# SCH.net
KiCad netlist of a schematic drawn in EasyEDA
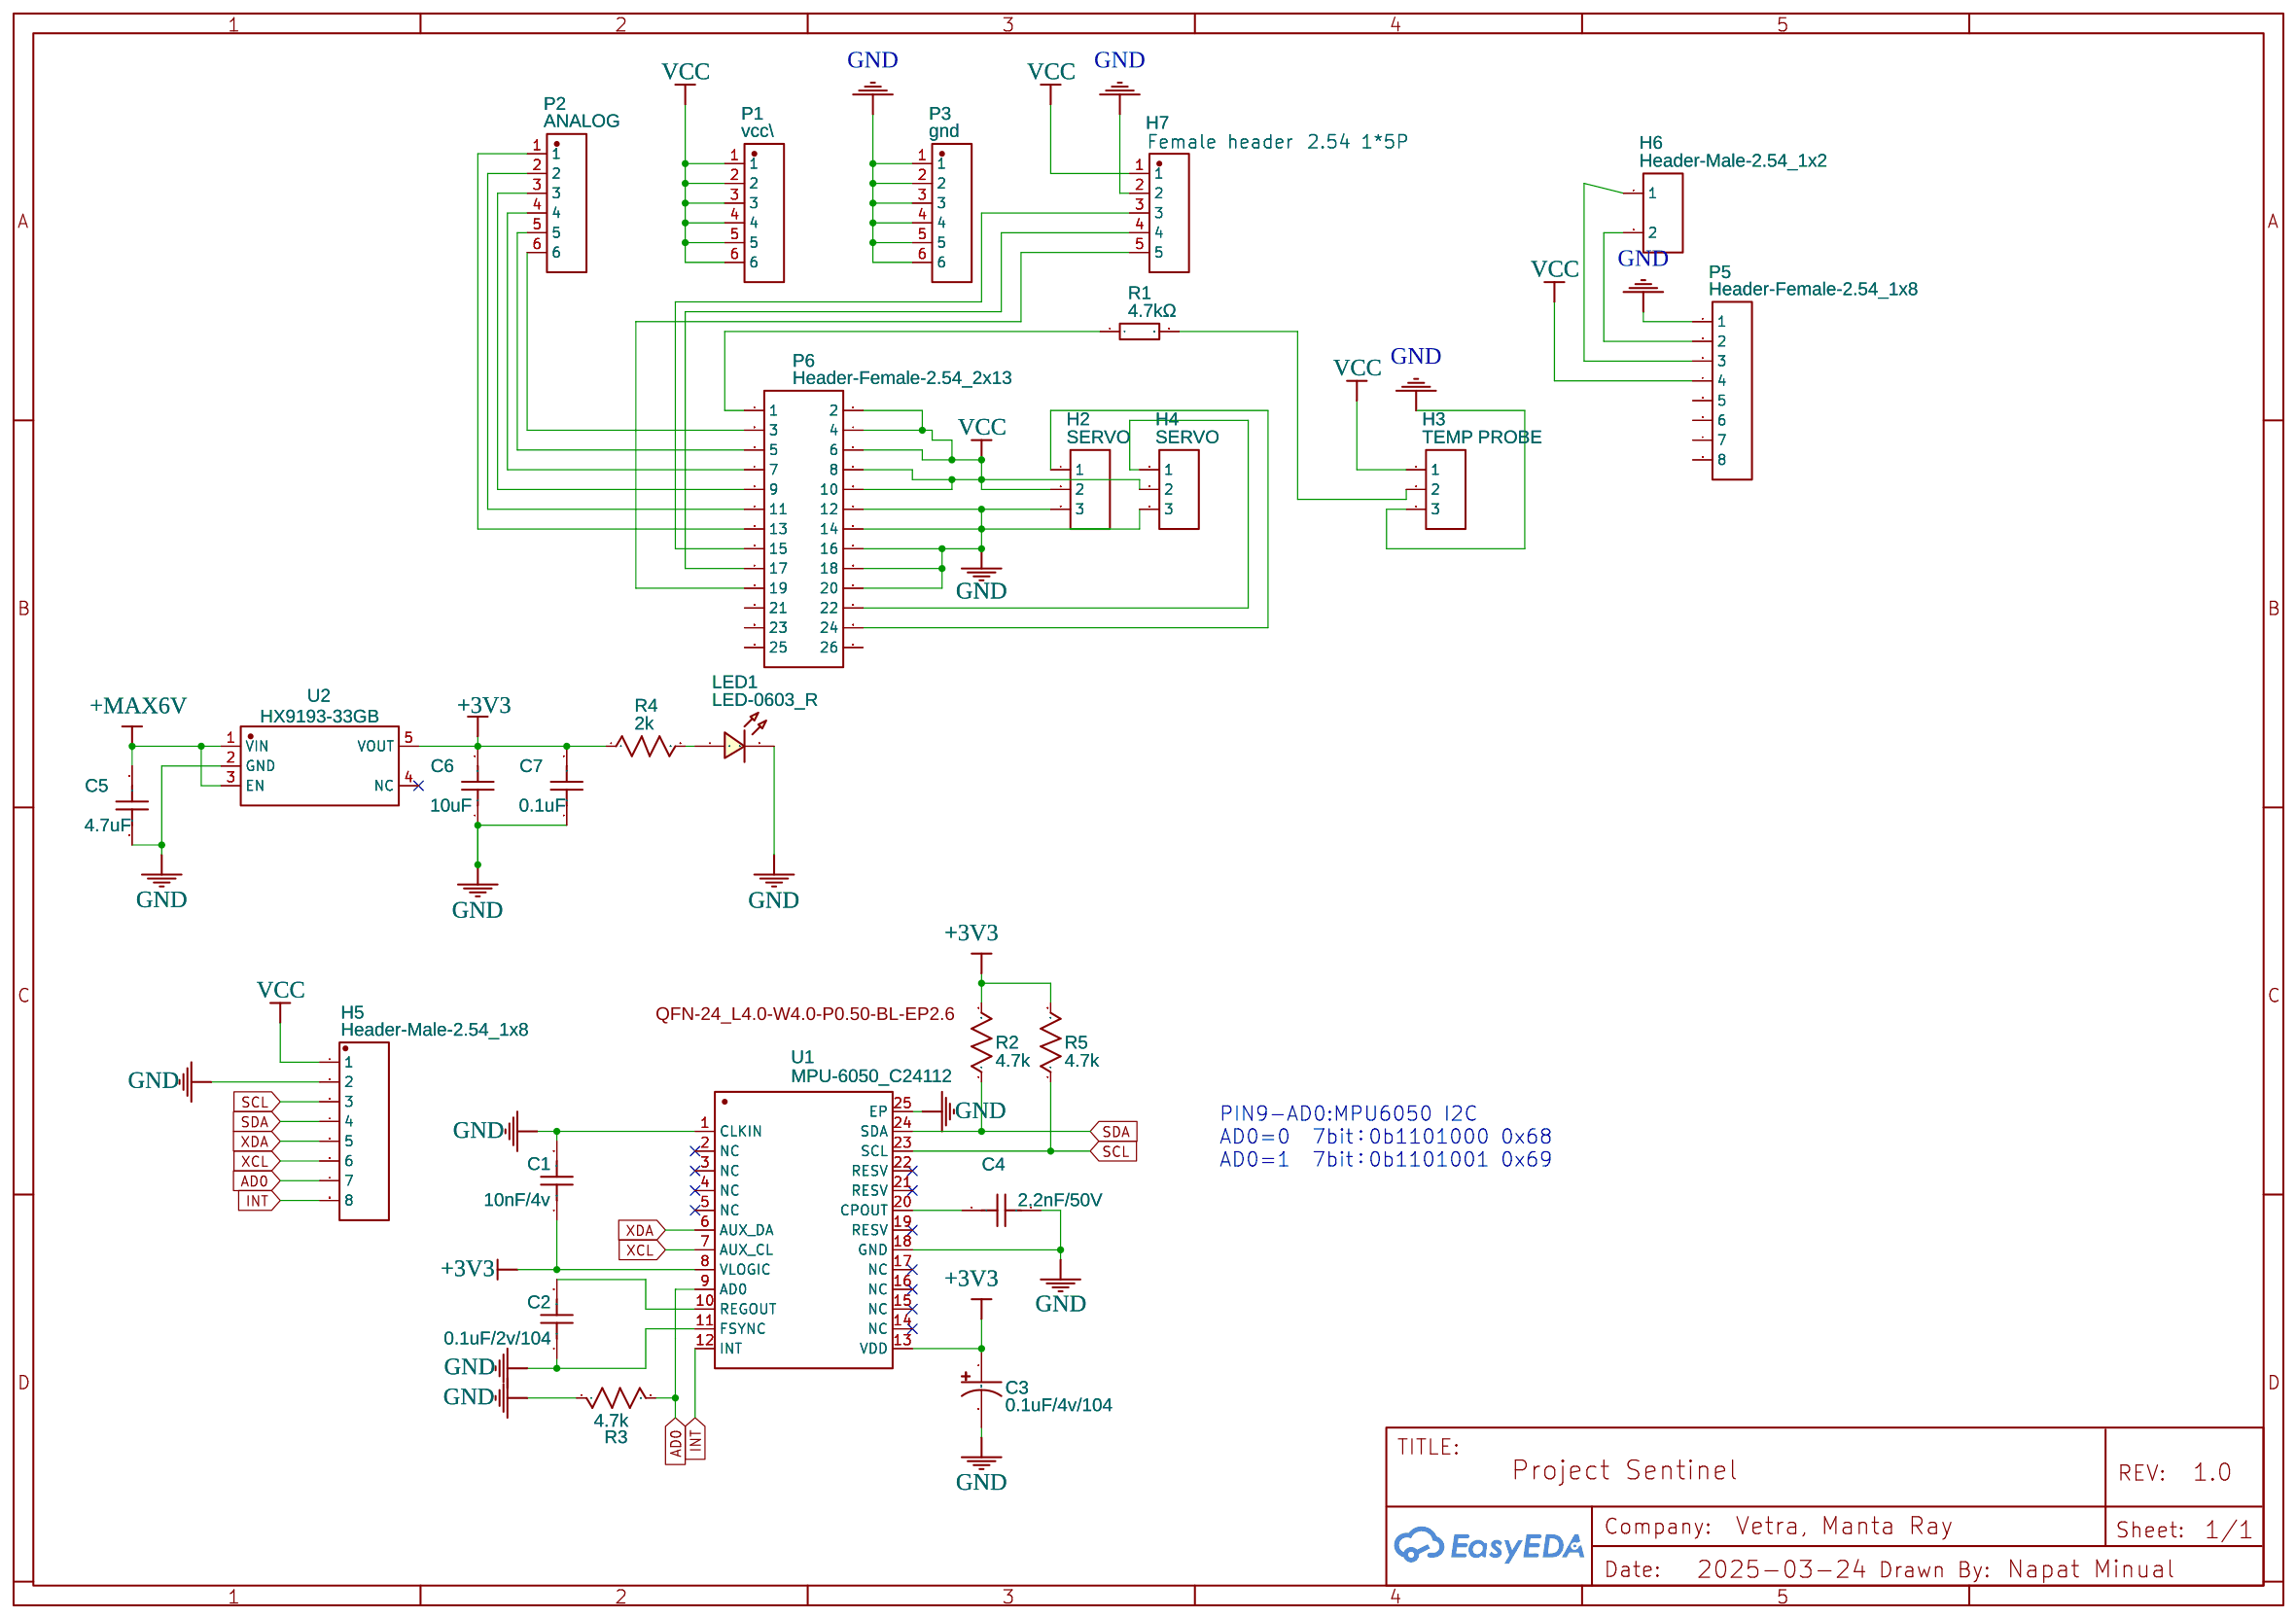
[diagram p0: schematic sheet]

(export (version "E")
  (design (tool "Eeschema 10.0.6"))
  (components
    (comp (ref "C1") (value "10nF/4v") (libsource (lib "") (part "C_0603_US_1")))
    (comp (ref "C2") (value "0.1uF/2v/104") (libsource (lib "") (part "C_0603_US_1")))
    (comp (ref "C3")
      (value "0.1uF/4v/104")
      (fields (field (name "Manufacturer Part") "TPSA106K016R1000") (field (name "Manufacturer") "AVX"))
      (libsource (lib "") (part "TPSA106K016R1000_C282116"))
    )
    (comp (ref "C4") (value "2.2nF/50V") (libsource (lib "") (part "C_0603_US")))
    (comp (ref "C5") (value "4.7uF") (libsource (lib "") (part "C_0603_US_1")))
    (comp (ref "C6") (value "10uF") (libsource (lib "") (part "C_0603_US_1")))
    (comp (ref "C7") (value "0.1uF") (libsource (lib "") (part "C_0603_US_1")))
    (comp (ref "H2")
      (value "SERVO")
      (fields (field (name "Manufacturer Part") "2.54-1*3P针") (field (name "Manufacturer") "BOOMELE(博穆精密)"))
      (libsource (lib "") (part "Header-Male-2.54_1x3"))
    )
    (comp (ref "H3")
      (value "TEMP PROBE")
      (fields (field (name "Manufacturer Part") "2.54-1*3P针") (field (name "Manufacturer") "BOOMELE(博穆精密)"))
      (libsource (lib "") (part "Header-Male-2.54_1x3"))
    )
    (comp (ref "H4")
      (value "SERVO")
      (fields (field (name "Manufacturer Part") "2.54-1*3P针") (field (name "Manufacturer") "BOOMELE(博穆精密)"))
      (libsource (lib "") (part "Header-Male-2.54_1x3"))
    )
    (comp (ref "H5")
      (value "Header-Male-2.54_1x8")
      (fields (field (name "Manufacturer Part") "B-2100S08P-A110") (field (name "Manufacturer") "Ckmtw(灿科盟)"))
      (libsource (lib "") (part "Header-Male-2.54_1x8"))
    )
    (comp (ref "H6")
      (value "Header-Male-2.54_1x2")
      (fields
        (field (name "Manufacturer Part") "826629-2")
        (field (name "Manufacturer") "TE Connectivity(泰科电子)")
      )
      (libsource (lib "") (part "Header-Male-2.54_1x2"))
    )
    (comp (ref "H7")
      (value "Female header　2.54 1*5Ｐ")
      (fields (field (name "Manufacturer Part") "排母　2.54 1*5Ｐ"))
      (libsource (lib "") (part "Female header　2.54 1*5Ｐ"))
    )
    (comp (ref "LED1")
      (value "LED-0603_R")
      (fields
        (field (name "Manufacturer Part") "19-217/R6C-AL1M2VY/3T")
        (field (name "Manufacturer") "EVERLIGHT(台湾亿光)")
      )
      (libsource (lib "") (part "LED-0603_R"))
    )
    (comp (ref "P1")
      (value "vcc\\")
      (fields (field (name "Manufacturer Part") "2.54-1*6P母") (field (name "Manufacturer") "BOOMELE(博穆精密)"))
      (libsource (lib "") (part "Header-Female-2.54_1x6"))
    )
    (comp (ref "P2")
      (value "ANALOG")
      (fields (field (name "Manufacturer Part") "2.54-1*6P母") (field (name "Manufacturer") "BOOMELE(博穆精密)"))
      (libsource (lib "") (part "Header-Female-2.54_1x6"))
    )
    (comp (ref "P3")
      (value "gnd")
      (fields (field (name "Manufacturer Part") "2.54-1*6P母") (field (name "Manufacturer") "BOOMELE(博穆精密)"))
      (libsource (lib "") (part "Header-Female-2.54_1x6"))
    )
    (comp (ref "P5")
      (value "Header-Female-2.54_1x8")
      (fields (field (name "Manufacturer Part") "2.54-1*8P母环保") (field (name "Manufacturer") "BOOMELE(博穆精密)"))
      (libsource (lib "") (part "Header-Female-2.54_1x8"))
    )
    (comp (ref "P6")
      (value "Header-Female-2.54_2x13")
      (fields (field (name "Manufacturer Part") "2.54-2*13P母") (field (name "Manufacturer") "BOOMELE(博穆精密)"))
      (libsource (lib "") (part "Header-Female-2.54_2x13"))
    )
    (comp (ref "R1")
      (value "4.7kΩ")
      (fields (field (name "Manufacturer Part") "RMC20104.7K1%N") (field (name "Manufacturer") "Tyohm(幸亚电阻)"))
      (libsource (lib "") (part "RMC20104.7K1%N"))
    )
    (comp (ref "R2") (value "4.7k") (libsource (lib "") (part "R_0603_US")))
    (comp (ref "R3") (value "4.7k") (libsource (lib "") (part "R_0603_US_1")))
    (comp (ref "R4") (value "2k") (libsource (lib "") (part "R_0603_US_2")))
    (comp (ref "R5") (value "4.7k") (libsource (lib "") (part "R_0603_US")))
    (comp (ref "U1")
      (value "MPU-6050_C24112")
      (fields (field (name "Manufacturer Part") "MPU-6050") (field (name "Manufacturer") "InvenSense"))
      (libsource (lib "") (part "MPU-6050_C24112"))
    )
    (comp (ref "U2")
      (value "HX9193-33GB")
      (fields (field (name "Manufacturer") "hengjiaxing"))
      (libsource (lib "") (part "HX9193-33GB"))
    )
  )
  (nets
    (net (code "1") (name "+3V3") (class "Default")
      (node (ref "C1") (pin "1") (pinfunction "1_1") (pintype "unspecified"))
      (node (ref "C3") (pin "1") (pinfunction "1_1") (pintype "unspecified"))
      (node (ref "C6") (pin "2") (pinfunction "2_2") (pintype "unspecified"))
      (node (ref "C7") (pin "2") (pinfunction "2_2") (pintype "unspecified"))
      (node (ref "R2") (pin "2") (pinfunction "2_2") (pintype "unspecified"))
      (node (ref "R4") (pin "1") (pinfunction "1_1") (pintype "unspecified"))
      (node (ref "R5") (pin "2") (pinfunction "2_2") (pintype "unspecified"))
      (node (ref "U1") (pin "13") (pinfunction "VDD_13") (pintype "unspecified"))
      (node (ref "U1") (pin "8") (pinfunction "VLOGIC_8") (pintype "unspecified"))
      (node (ref "U2") (pin "5") (pinfunction "VOUT_5") (pintype "unspecified"))
    )
    (net (code "2") (name "+MAX6V") (class "Default")
      (node (ref "C5") (pin "2") (pinfunction "2_2") (pintype "unspecified"))
      (node (ref "U2") (pin "1") (pinfunction "VIN_1") (pintype "unspecified"))
      (node (ref "U2") (pin "3") (pinfunction "EN_3") (pintype "unspecified"))
    )
    (net (code "3") (name "AD0") (class "Default")
      (node (ref "H5") (pin "7") (pinfunction "7_7") (pintype "unspecified"))
      (node (ref "R3") (pin "2") (pinfunction "2_2") (pintype "unspecified"))
      (node (ref "U1") (pin "9") (pinfunction "AD0_9") (pintype "unspecified"))
    )
    (net (code "4") (name "GND") (class "Default")
      (node (ref "C1") (pin "2") (pinfunction "2_2") (pintype "unspecified"))
      (node (ref "C2") (pin "1") (pinfunction "1_1") (pintype "unspecified"))
      (node (ref "C3") (pin "2") (pinfunction "2_2") (pintype "unspecified"))
      (node (ref "C4") (pin "1") (pinfunction "1_1") (pintype "unspecified"))
      (node (ref "C5") (pin "1") (pinfunction "1_1") (pintype "unspecified"))
      (node (ref "C6") (pin "1") (pinfunction "1_1") (pintype "unspecified"))
      (node (ref "C7") (pin "1") (pinfunction "1_1") (pintype "unspecified"))
      (node (ref "H2") (pin "3") (pinfunction "3_3") (pintype "input"))
      (node (ref "H3") (pin "3") (pinfunction "3_3") (pintype "input"))
      (node (ref "H4") (pin "3") (pinfunction "3_3") (pintype "input"))
      (node (ref "H5") (pin "2") (pinfunction "2_2") (pintype "unspecified"))
      (node (ref "H7") (pin "2") (pinfunction "2_2") (pintype "unspecified"))
      (node (ref "LED1") (pin "2") (pinfunction "2_2") (pintype "unspecified"))
      (node (ref "P3") (pin "1") (pinfunction "1_1") (pintype "unspecified"))
      (node (ref "P3") (pin "2") (pinfunction "2_2") (pintype "unspecified"))
      (node (ref "P3") (pin "3") (pinfunction "3_3") (pintype "unspecified"))
      (node (ref "P3") (pin "4") (pinfunction "4_4") (pintype "unspecified"))
      (node (ref "P3") (pin "5") (pinfunction "5_5") (pintype "unspecified"))
      (node (ref "P3") (pin "6") (pinfunction "6_6") (pintype "unspecified"))
      (node (ref "P5") (pin "1") (pinfunction "1_1") (pintype "input"))
      (node (ref "P6") (pin "12") (pinfunction "12_12") (pintype "input"))
      (node (ref "P6") (pin "14") (pinfunction "14_14") (pintype "input"))
      (node (ref "P6") (pin "16") (pinfunction "16_16") (pintype "input"))
      (node (ref "P6") (pin "18") (pinfunction "18_18") (pintype "input"))
      (node (ref "P6") (pin "20") (pinfunction "20_20") (pintype "input"))
      (node (ref "R3") (pin "1") (pinfunction "1_1") (pintype "unspecified"))
      (node (ref "U1") (pin "1") (pinfunction "CLKIN_1") (pintype "unspecified"))
      (node (ref "U1") (pin "11") (pinfunction "FSYNC_11") (pintype "unspecified"))
      (node (ref "U1") (pin "18") (pinfunction "GND_18") (pintype "unspecified"))
      (node (ref "U1") (pin "25") (pinfunction "EP_25") (pintype "unspecified"))
      (node (ref "U2") (pin "2") (pinfunction "GND_2") (pintype "unspecified"))
    )
    (net (code "5") (name "INT") (class "Default")
      (node (ref "H5") (pin "8") (pinfunction "8_8") (pintype "unspecified"))
      (node (ref "U1") (pin "12") (pinfunction "INT_12") (pintype "unspecified"))
    )
    (net (code "6") (name "Net-(H2-Pad1)") (class "Default")
      (node (ref "H2") (pin "1") (pinfunction "1_1") (pintype "input"))
      (node (ref "P6") (pin "24") (pinfunction "24_24") (pintype "input"))
    )
    (net (code "7") (name "Net-(H3-Pad2)") (class "Default")
      (node (ref "H3") (pin "2") (pinfunction "2_2") (pintype "input"))
      (node (ref "R1") (pin "2") (pinfunction "2_2") (pintype "unspecified"))
    )
    (net (code "8") (name "Net-(H4-Pad1)") (class "Default")
      (node (ref "H4") (pin "1") (pinfunction "1_1") (pintype "input"))
      (node (ref "P6") (pin "22") (pinfunction "22_22") (pintype "input"))
    )
    (net (code "9") (name "Net-(H6-Pad1)") (class "Default")
      (node (ref "H6") (pin "1") (pinfunction "1_1") (pintype "unspecified"))
      (node (ref "P5") (pin "3") (pinfunction "3_3") (pintype "input"))
    )
    (net (code "10") (name "Net-(H6-Pad2)") (class "Default")
      (node (ref "H6") (pin "2") (pinfunction "2_2") (pintype "unspecified"))
      (node (ref "P5") (pin "2") (pinfunction "2_2") (pintype "input"))
    )
    (net (code "11") (name "Net-(H7-Pad3)") (class "Default")
      (node (ref "H7") (pin "3") (pinfunction "3_3") (pintype "unspecified"))
      (node (ref "P6") (pin "15") (pinfunction "15_15") (pintype "input"))
    )
    (net (code "12") (name "Net-(H7-Pad4)") (class "Default")
      (node (ref "H7") (pin "4") (pinfunction "4_4") (pintype "unspecified"))
      (node (ref "P6") (pin "17") (pinfunction "17_17") (pintype "input"))
    )
    (net (code "13") (name "Net-(H7-Pad5)") (class "Default")
      (node (ref "H7") (pin "5") (pinfunction "5_5") (pintype "unspecified"))
      (node (ref "P6") (pin "19") (pinfunction "19_19") (pintype "input"))
    )
    (net (code "14") (name "Net-(LED1-Pad1)") (class "Default")
      (node (ref "LED1") (pin "1") (pinfunction "1_1") (pintype "unspecified"))
      (node (ref "R4") (pin "2") (pinfunction "2_2") (pintype "unspecified"))
    )
    (net (code "15") (name "Net-(P2-Pad1)") (class "Default")
      (node (ref "P2") (pin "1") (pinfunction "1_1") (pintype "unspecified"))
      (node (ref "P6") (pin "13") (pinfunction "13_13") (pintype "input"))
    )
    (net (code "16") (name "Net-(P2-Pad2)") (class "Default")
      (node (ref "P2") (pin "2") (pinfunction "2_2") (pintype "unspecified"))
      (node (ref "P6") (pin "11") (pinfunction "11_11") (pintype "input"))
    )
    (net (code "17") (name "Net-(P2-Pad3)") (class "Default")
      (node (ref "P2") (pin "3") (pinfunction "3_3") (pintype "unspecified"))
      (node (ref "P6") (pin "9") (pinfunction "9_9") (pintype "input"))
    )
    (net (code "18") (name "Net-(P2-Pad4)") (class "Default")
      (node (ref "P2") (pin "4") (pinfunction "4_4") (pintype "unspecified"))
      (node (ref "P6") (pin "7") (pinfunction "7_7") (pintype "input"))
    )
    (net (code "19") (name "Net-(P2-Pad5)") (class "Default")
      (node (ref "P2") (pin "5") (pinfunction "5_5") (pintype "unspecified"))
      (node (ref "P6") (pin "5") (pinfunction "5_5") (pintype "input"))
    )
    (net (code "20") (name "Net-(P2-Pad6)") (class "Default")
      (node (ref "P2") (pin "6") (pinfunction "6_6") (pintype "unspecified"))
      (node (ref "P6") (pin "3") (pinfunction "3_3") (pintype "input"))
    )
    (net (code "21") (name "Net-(P6-Pad1)") (class "Default")
      (node (ref "P6") (pin "1") (pinfunction "1_1") (pintype "input"))
      (node (ref "R1") (pin "1") (pinfunction "1_1") (pintype "unspecified"))
    )
    (net (code "22") (name "Net-(U1-CPOUT)") (class "Default")
      (node (ref "C4") (pin "2") (pinfunction "2_2") (pintype "unspecified"))
      (node (ref "U1") (pin "20") (pinfunction "CPOUT_20") (pintype "unspecified"))
    )
    (net (code "23") (name "Net-(U1-REGOUT)") (class "Default")
      (node (ref "C2") (pin "2") (pinfunction "2_2") (pintype "unspecified"))
      (node (ref "U1") (pin "10") (pinfunction "REGOUT_10") (pintype "unspecified"))
    )
    (net (code "24") (name "SCL") (class "Default")
      (node (ref "H5") (pin "3") (pinfunction "3_3") (pintype "unspecified"))
      (node (ref "R5") (pin "1") (pinfunction "1_1") (pintype "unspecified"))
      (node (ref "U1") (pin "23") (pinfunction "SCL_23") (pintype "unspecified"))
    )
    (net (code "25") (name "SDA") (class "Default")
      (node (ref "H5") (pin "4") (pinfunction "4_4") (pintype "unspecified"))
      (node (ref "R2") (pin "1") (pinfunction "1_1") (pintype "unspecified"))
      (node (ref "U1") (pin "24") (pinfunction "SDA_24") (pintype "unspecified"))
    )
    (net (code "26") (name "VCC") (class "Default")
      (node (ref "H2") (pin "2") (pinfunction "2_2") (pintype "input"))
      (node (ref "H3") (pin "1") (pinfunction "1_1") (pintype "input"))
      (node (ref "H4") (pin "2") (pinfunction "2_2") (pintype "input"))
      (node (ref "H5") (pin "1") (pinfunction "1_1") (pintype "unspecified"))
      (node (ref "H7") (pin "1") (pinfunction "1_1") (pintype "unspecified"))
      (node (ref "P1") (pin "1") (pinfunction "1_1") (pintype "unspecified"))
      (node (ref "P1") (pin "2") (pinfunction "2_2") (pintype "unspecified"))
      (node (ref "P1") (pin "3") (pinfunction "3_3") (pintype "unspecified"))
      (node (ref "P1") (pin "4") (pinfunction "4_4") (pintype "unspecified"))
      (node (ref "P1") (pin "5") (pinfunction "5_5") (pintype "unspecified"))
      (node (ref "P1") (pin "6") (pinfunction "6_6") (pintype "unspecified"))
      (node (ref "P5") (pin "4") (pinfunction "4_4") (pintype "input"))
      (node (ref "P6") (pin "10") (pinfunction "10_10") (pintype "input"))
      (node (ref "P6") (pin "2") (pinfunction "2_2") (pintype "input"))
      (node (ref "P6") (pin "4") (pinfunction "4_4") (pintype "input"))
      (node (ref "P6") (pin "6") (pinfunction "6_6") (pintype "input"))
      (node (ref "P6") (pin "8") (pinfunction "8_8") (pintype "input"))
    )
    (net (code "27") (name "XCL") (class "Default")
      (node (ref "H5") (pin "6") (pinfunction "6_6") (pintype "unspecified"))
      (node (ref "U1") (pin "7") (pinfunction "AUX_CL_7") (pintype "unspecified"))
    )
    (net (code "28") (name "XDA") (class "Default")
      (node (ref "H5") (pin "5") (pinfunction "5_5") (pintype "unspecified"))
      (node (ref "U1") (pin "6") (pinfunction "AUX_DA_6") (pintype "unspecified"))
    )
    (net (code "29") (name "unconnected-(P5-Pad5)") (class "Default")
      (node (ref "P5") (pin "5") (pinfunction "5_5") (pintype "input"))
    )
    (net (code "30") (name "unconnected-(P5-Pad6)") (class "Default")
      (node (ref "P5") (pin "6") (pinfunction "6_6") (pintype "input"))
    )
    (net (code "31") (name "unconnected-(P5-Pad7)") (class "Default")
      (node (ref "P5") (pin "7") (pinfunction "7_7") (pintype "input"))
    )
    (net (code "32") (name "unconnected-(P5-Pad8)") (class "Default")
      (node (ref "P5") (pin "8") (pinfunction "8_8") (pintype "input"))
    )
    (net (code "33") (name "unconnected-(P6-Pad21)") (class "Default")
      (node (ref "P6") (pin "21") (pinfunction "21_21") (pintype "input"))
    )
    (net (code "34") (name "unconnected-(P6-Pad23)") (class "Default")
      (node (ref "P6") (pin "23") (pinfunction "23_23") (pintype "input"))
    )
    (net (code "35") (name "unconnected-(P6-Pad25)") (class "Default")
      (node (ref "P6") (pin "25") (pinfunction "25_25") (pintype "input"))
    )
    (net (code "36") (name "unconnected-(P6-Pad26)") (class "Default")
      (node (ref "P6") (pin "26") (pinfunction "26_26") (pintype "input"))
    )
    (net (code "37") (name "unconnected-(U1-NC-Pad2)") (class "Default")
      (node (ref "U1") (pin "2") (pinfunction "NC_2") (pintype "unspecified+no_connect"))
    )
    (net (code "38") (name "unconnected-(U1-NC-Pad3)") (class "Default")
      (node (ref "U1") (pin "3") (pinfunction "NC_3") (pintype "unspecified+no_connect"))
    )
    (net (code "39") (name "unconnected-(U1-NC-Pad4)") (class "Default")
      (node (ref "U1") (pin "4") (pinfunction "NC_4") (pintype "unspecified+no_connect"))
    )
    (net (code "40") (name "unconnected-(U1-NC-Pad5)") (class "Default")
      (node (ref "U1") (pin "5") (pinfunction "NC_5") (pintype "unspecified+no_connect"))
    )
    (net (code "41") (name "unconnected-(U1-NC-Pad14)") (class "Default")
      (node (ref "U1") (pin "14") (pinfunction "NC_14") (pintype "unspecified+no_connect"))
    )
    (net (code "42") (name "unconnected-(U1-NC-Pad15)") (class "Default")
      (node (ref "U1") (pin "15") (pinfunction "NC_15") (pintype "unspecified+no_connect"))
    )
    (net (code "43") (name "unconnected-(U1-NC-Pad16)") (class "Default")
      (node (ref "U1") (pin "16") (pinfunction "NC_16") (pintype "unspecified+no_connect"))
    )
    (net (code "44") (name "unconnected-(U1-NC-Pad17)") (class "Default")
      (node (ref "U1") (pin "17") (pinfunction "NC_17") (pintype "unspecified+no_connect"))
    )
    (net (code "45") (name "unconnected-(U1-RESV-Pad19)") (class "Default")
      (node (ref "U1") (pin "19") (pinfunction "RESV_19") (pintype "unspecified+no_connect"))
    )
    (net (code "46") (name "unconnected-(U1-RESV-Pad21)") (class "Default")
      (node (ref "U1") (pin "21") (pinfunction "RESV_21") (pintype "unspecified+no_connect"))
    )
    (net (code "47") (name "unconnected-(U1-RESV-Pad22)") (class "Default")
      (node (ref "U1") (pin "22") (pinfunction "RESV_22") (pintype "unspecified+no_connect"))
    )
    (net (code "48") (name "unconnected-(U2-NC-Pad4)") (class "Default")
      (node (ref "U2") (pin "4") (pinfunction "NC_4") (pintype "unspecified+no_connect"))
    )
  )
)
